# Lora-IO-Device.net
KiCad netlist of a schematic drawn in Altium Designer
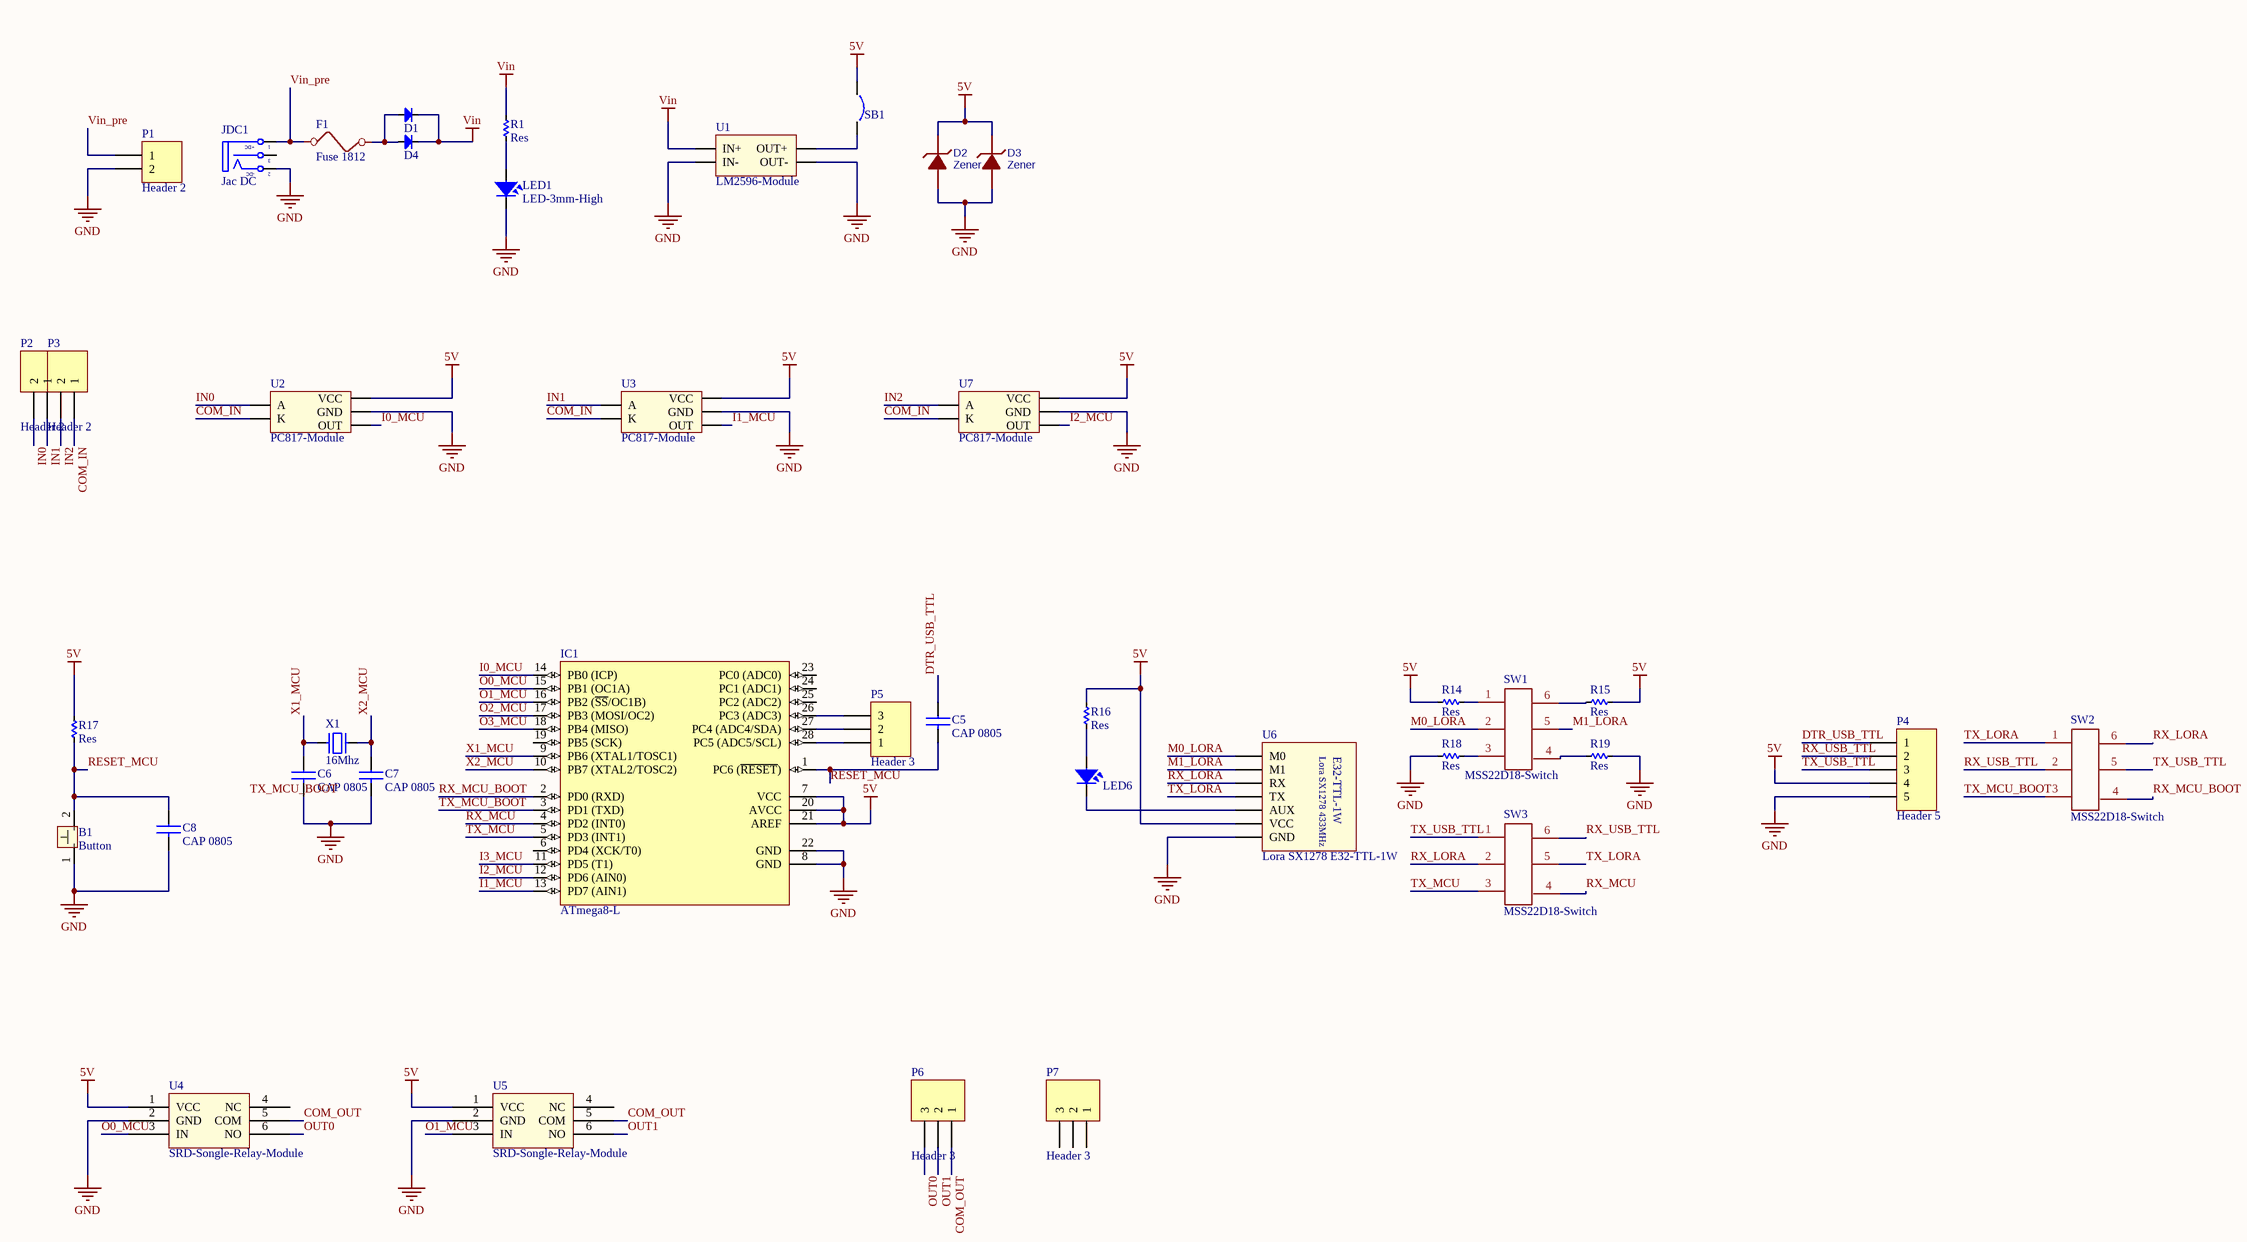
[diagram p0: Lora-IO-Device.SchDoc]

(export (version "E")
  (design (tool "Eeschema 10.0.6"))
  (components
    (comp (ref "B1")
      (value "Button")
      (footprint "Button")
      (description "Button 6x6 SMD 4 pin")
      (libsource (lib "Button SMD 6x6 4 pin") (part "Button"))
    )
    (comp (ref "C5") (value "CAP 0805") (footprint "0805") (libsource (lib "Cty1") (part "CAP 0805")))
    (comp (ref "C6") (value "CAP 0805") (footprint "0805") (libsource (lib "Cty1") (part "CAP 0805")))
    (comp (ref "C7") (value "CAP 0805") (footprint "0805") (libsource (lib "Cty1") (part "CAP 0805")))
    (comp (ref "C8") (value "CAP 0805") (footprint "0805") (libsource (lib "Cty1") (part "CAP 0805")))
    (comp (ref "D1")
      (value "Diode SMD")
      (footprint "DIO-SMD-106")
      (description "Default Diode")
      (fields (field (name "PUBLISHER") "Altium Limited"))
      (libsource (lib "Thư Viện Altium FULL HD") (part "Diode SMD"))
    )
    (comp (ref "D2")
      (value "Zener")
      (footprint "SOD80C")
      (fields
        (field (name "BOM_SUPPLIER PART") "C108433")
        (field (name "BOM_MANUFACTURER PART") "BZV55-C15")
        (field (name "CONTRIBUTOR") "LCSC")
      )
      (libsource (lib "Zener-Diode") (part "Zener"))
    )
    (comp (ref "D3")
      (value "Zener")
      (footprint "SOD80C")
      (fields
        (field (name "BOM_SUPPLIER PART") "C108433")
        (field (name "BOM_MANUFACTURER PART") "BZV55-C15")
        (field (name "CONTRIBUTOR") "LCSC")
      )
      (libsource (lib "Zener-Diode") (part "Zener"))
    )
    (comp (ref "D4")
      (value "Diode SMD")
      (footprint "DIO-SMD-106")
      (description "Default Diode")
      (fields (field (name "PUBLISHER") "Altium Limited"))
      (libsource (lib "Thư Viện Altium FULL HD") (part "Diode SMD"))
    )
    (comp (ref "F1")
      (value "Fuse 1812")
      (footprint "Fuse-1812")
      (libsource (lib "Fuse-1812") (part "Fuse-1812"))
    )
    (comp (ref "IC1")
      (value "ATmega8-L")
      (footprint "DIP28/W0.3")
      (description "8-Bit AVR Microcontroller with 8K Bytes of In-System Programmable Flash Memory")
      (libsource (lib "hphonglib") (part "ATmega8-L"))
    )
    (comp (ref "JDC1")
      (value "Jac DC")
      (footprint "DC0")
      (description "Jac DC input")
      (libsource (lib "Thư Viện Altium FULL HD") (part "DCIN"))
    )
    (comp (ref "LED1")
      (value "LED-3mm-High")
      (footprint "LED-3mm-High-Green")
      (libsource (lib "LED-3mm-High") (part "LED-3mm-High"))
    )
    (comp (ref "LED6")
      (value "LED")
      (footprint "LED-0805-Orange")
      (libsource (lib "Thư Viện Altium FULL HD") (part "LED SMD"))
    )
    (comp (ref "P1")
      (value "Header 2")
      (footprint "TBlock 2")
      (description "Header, 2-Pin")
      (fields (field (name "PUBLISHER") "Altium Limited"))
      (libsource (lib "hphonglib") (part "Header 2"))
    )
    (comp (ref "P2")
      (value "Header 2")
      (footprint "TBlock 2")
      (description "Header, 2-Pin")
      (fields (field (name "PUBLISHER") "Altium Limited"))
      (libsource (lib "hphonglib") (part "Header 2"))
    )
    (comp (ref "P3")
      (value "Header 2")
      (footprint "TBlock 2")
      (description "Header, 2-Pin")
      (fields (field (name "PUBLISHER") "Altium Limited"))
      (libsource (lib "hphonglib") (part "Header 2"))
    )
    (comp (ref "P4")
      (value "Header 5")
      (footprint "Header 5-V")
      (description "Header, 5-Pin")
      (fields (field (name "PUBLISHER") "Altium Limited"))
      (libsource (lib "hphonglib") (part "Header 5"))
    )
    (comp (ref "P5")
      (value "Header 3")
      (footprint "TBlock 3")
      (description "Header, 3-Pin")
      (fields (field (name "PUBLISHER") "Altium Limited"))
      (libsource (lib "") (part "Header 3_1"))
    )
    (comp (ref "P6")
      (value "Header 3")
      (footprint "TBlock 3")
      (description "Header, 3-Pin")
      (fields (field (name "PUBLISHER") "Altium Limited"))
      (libsource (lib "hphonglib") (part "Header 3"))
    )
    (comp (ref "P7")
      (value "Header 3")
      (footprint "TBlock 3")
      (description "Header, 3-Pin")
      (fields (field (name "PUBLISHER") "Altium Limited"))
      (libsource (lib "hphonglib") (part "Header 3"))
    )
    (comp (ref "R1")
      (value "Res")
      (footprint "RES-SMD-0805")
      (description "Resistor")
      (fields
        (field (name "MANUFACTURER") "Generic Components")
        (field (name "PUBLISHER") "Altium Hobart Technology Centre")
      )
      (libsource (lib "Thư Viện Altium FULL HD") (part "Res-SMD"))
    )
    (comp (ref "R14")
      (value "Res")
      (footprint "RES-SMD-0805")
      (description "Resistor")
      (fields
        (field (name "MANUFACTURER") "Generic Components")
        (field (name "PUBLISHER") "Altium Hobart Technology Centre")
      )
      (libsource (lib "Thư Viện Altium FULL HD") (part "Res-SMD"))
    )
    (comp (ref "R15")
      (value "Res")
      (footprint "RES-SMD-0805")
      (description "Resistor")
      (fields
        (field (name "MANUFACTURER") "Generic Components")
        (field (name "PUBLISHER") "Altium Hobart Technology Centre")
      )
      (libsource (lib "Thư Viện Altium FULL HD") (part "Res-SMD"))
    )
    (comp (ref "R16")
      (value "Res")
      (footprint "RES-SMD-0805")
      (description "Resistor")
      (fields
        (field (name "MANUFACTURER") "Generic Components")
        (field (name "PUBLISHER") "Altium Hobart Technology Centre")
      )
      (libsource (lib "Thư Viện Altium FULL HD") (part "Res-SMD"))
    )
    (comp (ref "R17")
      (value "Res")
      (footprint "RES-SMD-0805")
      (description "Resistor")
      (fields
        (field (name "MANUFACTURER") "Generic Components")
        (field (name "PUBLISHER") "Altium Hobart Technology Centre")
      )
      (libsource (lib "Thư Viện Altium FULL HD") (part "Res-SMD"))
    )
    (comp (ref "R18")
      (value "Res")
      (footprint "RES-SMD-0805")
      (description "Resistor")
      (fields
        (field (name "MANUFACTURER") "Generic Components")
        (field (name "PUBLISHER") "Altium Hobart Technology Centre")
      )
      (libsource (lib "Thư Viện Altium FULL HD") (part "Res-SMD"))
    )
    (comp (ref "R19")
      (value "Res")
      (footprint "RES-SMD-0805")
      (description "Resistor")
      (fields
        (field (name "MANUFACTURER") "Generic Components")
        (field (name "PUBLISHER") "Altium Hobart Technology Centre")
      )
      (libsource (lib "Thư Viện Altium FULL HD") (part "Res-SMD"))
    )
    (comp (ref "SB1")
      (value "Circuit-Shorter")
      (footprint "Circuit-Shorter")
      (fields (field (name "PUBLISHER") "Altium Limited"))
      (libsource (lib "Circuit-Shorter") (part "Circuit-Shorter"))
    )
    (comp (ref "SW1")
      (value "MSS22D18-Switch")
      (footprint "MSS22D18-Switch-SMD")
      (libsource (lib "MSS22D18-Switch") (part "MSS22D18-Switch"))
    )
    (comp (ref "SW2")
      (value "MSS22D18-Switch")
      (footprint "MSS22D18-Switch-SMD")
      (libsource (lib "MSS22D18-Switch") (part "MSS22D18-Switch"))
    )
    (comp (ref "SW3")
      (value "MSS22D18-Switch")
      (footprint "MSS22D18-Switch-SMD")
      (libsource (lib "MSS22D18-Switch") (part "MSS22D18-Switch"))
    )
    (comp (ref "U1")
      (value "LM2596-Module")
      (footprint "LM2596-Module-2")
      (libsource (lib "LM2596-Module") (part "LM2596-Module"))
    )
    (comp (ref "U2")
      (value "PC817-Module")
      (footprint "PC817-Module-1")
      (libsource (lib "PC817-Module") (part "PC817-Module"))
    )
    (comp (ref "U3")
      (value "PC817-Module")
      (footprint "PC817-Module-1")
      (libsource (lib "PC817-Module") (part "PC817-Module"))
    )
    (comp (ref "U4")
      (value "SRD-Songle-Relay-Module")
      (footprint "SRD-Songle-Relay-Module-1")
      (libsource (lib "SRD-Songle-Relay-Module") (part "SRD-Songle-Relay-Module"))
    )
    (comp (ref "U5")
      (value "SRD-Songle-Relay-Module")
      (footprint "SRD-Songle-Relay-Module-1")
      (libsource (lib "SRD-Songle-Relay-Module") (part "SRD-Songle-Relay-Module"))
    )
    (comp (ref "U6")
      (value "Lora SX1278 E32-TTL-1W")
      (footprint "Lora SX1278 E32-TTL-1W")
      (libsource (lib "Lora SX1278 E32-TTL-1W") (part "Lora SX1278 E32-TTL-1W"))
    )
    (comp (ref "U7")
      (value "PC817-Module")
      (footprint "PC817-Module-1")
      (libsource (lib "PC817-Module") (part "PC817-Module"))
    )
    (comp (ref "X1")
      (value "16Mhz")
      (footprint "XTAL-RU49/4")
      (description "Crystal, 32.768 KHz, -40 to 85 degC, 3.2 x 1.5 x 0.9 mm SMD")
      (libsource (lib "Thư Viện Altium FULL HD") (part "XT2"))
    )
  )
  (nets
    (net (code "1") (name "/COM_IN") (class "Default")
      (node (ref "P3") (pin "1") (pinfunction "1_1") (pintype "passive"))
      (node (ref "U2") (pin "2") (pinfunction "K_2") (pintype "passive"))
      (node (ref "U3") (pin "2") (pinfunction "K_2") (pintype "passive"))
      (node (ref "U7") (pin "2") (pinfunction "K_2") (pintype "passive"))
    )
    (net (code "2") (name "/COM_OUT") (class "Default")
      (node (ref "P6") (pin "1") (pinfunction "1_1") (pintype "passive"))
      (node (ref "U4") (pin "5") (pinfunction "COM_5") (pintype "passive"))
      (node (ref "U5") (pin "5") (pinfunction "COM_5") (pintype "passive"))
    )
    (net (code "3") (name "/DTR_USB_TTL") (class "Default")
      (node (ref "C5") (pin "1") (pinfunction "1_1") (pintype "passive"))
      (node (ref "P4") (pin "1") (pinfunction "1_1") (pintype "passive"))
    )
    (net (code "4") (name "/I0_MCU") (class "Default")
      (node (ref "IC1") (pin "14") (pinfunction "PB0_(ICP)_14") (pintype "bidirectional"))
      (node (ref "U2") (pin "5") (pinfunction "OUT_5") (pintype "passive"))
    )
    (net (code "5") (name "/I1_MCU") (class "Default")
      (node (ref "IC1") (pin "13") (pinfunction "PD7_(AIN1)_13") (pintype "bidirectional"))
      (node (ref "U3") (pin "5") (pinfunction "OUT_5") (pintype "passive"))
    )
    (net (code "6") (name "/I2_MCU") (class "Default")
      (node (ref "IC1") (pin "12") (pinfunction "PD6_(AIN0)_12") (pintype "bidirectional"))
      (node (ref "U7") (pin "5") (pinfunction "OUT_5") (pintype "passive"))
    )
    (net (code "7") (name "/I3_MCU") (class "Default")
      (node (ref "IC1") (pin "11") (pinfunction "PD5_(T1)_11") (pintype "bidirectional"))
    )
    (net (code "8") (name "/IN0") (class "Default")
      (node (ref "P2") (pin "2") (pinfunction "2_2") (pintype "passive"))
      (node (ref "U2") (pin "1") (pinfunction "A_1") (pintype "passive"))
    )
    (net (code "9") (name "/IN1") (class "Default")
      (node (ref "P2") (pin "1") (pinfunction "1_1") (pintype "passive"))
      (node (ref "U3") (pin "1") (pinfunction "A_1") (pintype "passive"))
    )
    (net (code "10") (name "/IN2") (class "Default")
      (node (ref "P3") (pin "2") (pinfunction "2_2") (pintype "passive"))
      (node (ref "U7") (pin "1") (pinfunction "A_1") (pintype "passive"))
    )
    (net (code "11") (name "/M0_LORA") (class "Default")
      (node (ref "SW1") (pin "2") (pinfunction "2_2") (pintype "passive"))
      (node (ref "U6") (pin "1") (pinfunction "M0_1") (pintype "passive"))
    )
    (net (code "12") (name "/M1_LORA") (class "Default")
      (node (ref "SW1") (pin "5") (pinfunction "5_5") (pintype "passive"))
      (node (ref "U6") (pin "2") (pinfunction "M1_2") (pintype "passive"))
    )
    (net (code "13") (name "/O0_MCU") (class "Default")
      (node (ref "IC1") (pin "15") (pinfunction "PB1_(OC1A)_15") (pintype "bidirectional"))
      (node (ref "U4") (pin "3") (pinfunction "IN_3") (pintype "passive"))
    )
    (net (code "14") (name "/O1_MCU") (class "Default")
      (node (ref "IC1") (pin "16") (pinfunction "PB2_(~{SS}/OC1B)_16") (pintype "bidirectional"))
      (node (ref "U5") (pin "3") (pinfunction "IN_3") (pintype "passive"))
    )
    (net (code "15") (name "/O2_MCU") (class "Default")
      (node (ref "IC1") (pin "17") (pinfunction "PB3_(MOSI/OC2)_17") (pintype "bidirectional"))
    )
    (net (code "16") (name "/O3_MCU") (class "Default")
      (node (ref "IC1") (pin "18") (pinfunction "PB4_(MISO)_18") (pintype "bidirectional"))
    )
    (net (code "17") (name "/OUT0") (class "Default")
      (node (ref "P6") (pin "3") (pinfunction "3_3") (pintype "passive"))
      (node (ref "U4") (pin "6") (pinfunction "NO_6") (pintype "passive"))
    )
    (net (code "18") (name "/OUT1") (class "Default")
      (node (ref "P6") (pin "2") (pinfunction "2_2") (pintype "passive"))
      (node (ref "U5") (pin "6") (pinfunction "NO_6") (pintype "passive"))
    )
    (net (code "19") (name "/RESET_MCU") (class "Default")
      (node (ref "B1") (pin "2") (pinfunction "2_2") (pintype "passive"))
      (node (ref "C5") (pin "2") (pinfunction "2_2") (pintype "passive"))
      (node (ref "C8") (pin "1") (pinfunction "1_1") (pintype "passive"))
      (node (ref "IC1") (pin "1") (pinfunction "PC6_(~{RESET})_1") (pintype "bidirectional"))
      (node (ref "R17") (pin "2") (pinfunction "2_2") (pintype "passive"))
    )
    (net (code "20") (name "/RX_LORA") (class "Default")
      (node (ref "SW2") (pin "6") (pinfunction "6_6") (pintype "passive"))
      (node (ref "SW3") (pin "2") (pinfunction "2_2") (pintype "passive"))
      (node (ref "U6") (pin "3") (pinfunction "RX_3") (pintype "passive"))
    )
    (net (code "21") (name "/RX_MCU") (class "Default")
      (node (ref "IC1") (pin "4") (pinfunction "PD2_(INT0)_4") (pintype "bidirectional"))
      (node (ref "SW3") (pin "4") (pinfunction "4_4") (pintype "passive"))
    )
    (net (code "22") (name "/RX_MCU_BOOT") (class "Default")
      (node (ref "IC1") (pin "2") (pinfunction "PD0_(RXD)_2") (pintype "bidirectional"))
      (node (ref "SW2") (pin "4") (pinfunction "4_4") (pintype "passive"))
    )
    (net (code "23") (name "/RX_USB_TTL") (class "Default")
      (node (ref "P4") (pin "2") (pinfunction "2_2") (pintype "passive"))
      (node (ref "SW2") (pin "2") (pinfunction "2_2") (pintype "passive"))
      (node (ref "SW3") (pin "6") (pinfunction "6_6") (pintype "passive"))
    )
    (net (code "24") (name "/TX_LORA") (class "Default")
      (node (ref "SW2") (pin "1") (pinfunction "1_1") (pintype "passive"))
      (node (ref "SW3") (pin "5") (pinfunction "5_5") (pintype "passive"))
      (node (ref "U6") (pin "4") (pinfunction "TX_4") (pintype "passive"))
    )
    (net (code "25") (name "/TX_MCU") (class "Default")
      (node (ref "IC1") (pin "5") (pinfunction "PD3_(INT1)_5") (pintype "bidirectional"))
      (node (ref "SW3") (pin "3") (pinfunction "3_3") (pintype "passive"))
    )
    (net (code "26") (name "/TX_MCU_BOOT") (class "Default")
      (node (ref "IC1") (pin "3") (pinfunction "PD1_(TXD)_3") (pintype "bidirectional"))
      (node (ref "SW2") (pin "3") (pinfunction "3_3") (pintype "passive"))
    )
    (net (code "27") (name "/TX_USB_TTL") (class "Default")
      (node (ref "P4") (pin "3") (pinfunction "3_3") (pintype "passive"))
      (node (ref "SW2") (pin "5") (pinfunction "5_5") (pintype "passive"))
      (node (ref "SW3") (pin "1") (pinfunction "1_1") (pintype "passive"))
    )
    (net (code "28") (name "/Vin_pre") (class "Default")
      (node (ref "F1") (pin "1") (pinfunction "1_1") (pintype "passive"))
      (node (ref "JDC1") (pin "1") (pinfunction "T_1") (pintype "passive"))
      (node (ref "P1") (pin "1") (pinfunction "1_1") (pintype "passive"))
    )
    (net (code "29") (name "/X1_MCU") (class "Default")
      (node (ref "C6") (pin "1") (pinfunction "1_1") (pintype "passive"))
      (node (ref "IC1") (pin "9") (pinfunction "PB6_(XTAL1/TOSC1)_9") (pintype "bidirectional"))
      (node (ref "X1") (pin "1") (pinfunction "1_1") (pintype "passive"))
    )
    (net (code "30") (name "/X2_MCU") (class "Default")
      (node (ref "C7") (pin "1") (pinfunction "1_1") (pintype "passive"))
      (node (ref "IC1") (pin "10") (pinfunction "PB7_(XTAL2/TOSC2)_10") (pintype "bidirectional"))
      (node (ref "X1") (pin "2") (pinfunction "2_2") (pintype "passive"))
    )
    (net (code "31") (name "5V") (class "Default")
      (node (ref "D2") (pin "2") (pinfunction "K_2") (pintype "passive"))
      (node (ref "D3") (pin "2") (pinfunction "K_2") (pintype "passive"))
      (node (ref "IC1") (pin "20") (pinfunction "AVCC_20") (pintype "power_in"))
      (node (ref "IC1") (pin "21") (pinfunction "AREF_21") (pintype "passive"))
      (node (ref "IC1") (pin "7") (pinfunction "VCC_7") (pintype "power_in"))
      (node (ref "P4") (pin "4") (pinfunction "4_4") (pintype "passive"))
      (node (ref "R14") (pin "2") (pinfunction "2_2") (pintype "passive"))
      (node (ref "R15") (pin "1") (pinfunction "1_1") (pintype "passive"))
      (node (ref "R16") (pin "1") (pinfunction "1_1") (pintype "passive"))
      (node (ref "R17") (pin "1") (pinfunction "1_1") (pintype "passive"))
      (node (ref "SB1") (pin "1") (pinfunction "1_1") (pintype "passive"))
      (node (ref "U2") (pin "3") (pinfunction "VCC_3") (pintype "passive"))
      (node (ref "U3") (pin "3") (pinfunction "VCC_3") (pintype "passive"))
      (node (ref "U4") (pin "1") (pinfunction "VCC_1") (pintype "passive"))
      (node (ref "U5") (pin "1") (pinfunction "VCC_1") (pintype "passive"))
      (node (ref "U6") (pin "6") (pinfunction "VCC_6") (pintype "passive"))
      (node (ref "U7") (pin "3") (pinfunction "VCC_3") (pintype "passive"))
    )
    (net (code "32") (name "GND") (class "Default")
      (node (ref "B1") (pin "1") (pinfunction "1_1") (pintype "passive"))
      (node (ref "C6") (pin "2") (pinfunction "2_2") (pintype "passive"))
      (node (ref "C7") (pin "2") (pinfunction "2_2") (pintype "passive"))
      (node (ref "C8") (pin "2") (pinfunction "2_2") (pintype "passive"))
      (node (ref "D2") (pin "1") (pinfunction "A_1") (pintype "passive"))
      (node (ref "D3") (pin "1") (pinfunction "A_1") (pintype "passive"))
      (node (ref "IC1") (pin "22") (pinfunction "GND_22") (pintype "power_in"))
      (node (ref "IC1") (pin "8") (pinfunction "GND_8") (pintype "power_in"))
      (node (ref "JDC1") (pin "2") (pinfunction "TN_2") (pintype "passive"))
      (node (ref "LED1") (pin "2") (pinfunction "K_2") (pintype "passive"))
      (node (ref "P1") (pin "2") (pinfunction "2_2") (pintype "passive"))
      (node (ref "P4") (pin "5") (pinfunction "5_5") (pintype "passive"))
      (node (ref "R18") (pin "2") (pinfunction "2_2") (pintype "passive"))
      (node (ref "R19") (pin "1") (pinfunction "1_1") (pintype "passive"))
      (node (ref "U1") (pin "IN-") (pinfunction "IN-_IN-") (pintype "passive"))
      (node (ref "U1") (pin "OUT-") (pinfunction "OUT-_OUT-") (pintype "passive"))
      (node (ref "U2") (pin "4") (pinfunction "GND_4") (pintype "passive"))
      (node (ref "U3") (pin "4") (pinfunction "GND_4") (pintype "passive"))
      (node (ref "U4") (pin "2") (pinfunction "GND_2") (pintype "passive"))
      (node (ref "U5") (pin "2") (pinfunction "GND_2") (pintype "passive"))
      (node (ref "U6") (pin "7") (pinfunction "GND_7") (pintype "passive"))
      (node (ref "U7") (pin "4") (pinfunction "GND_4") (pintype "passive"))
    )
    (net (code "33") (name "Net-(D1-A)") (class "Default")
      (node (ref "D1") (pin "1") (pinfunction "A_1") (pintype "passive"))
      (node (ref "D4") (pin "1") (pinfunction "A_1") (pintype "passive"))
      (node (ref "F1") (pin "2") (pinfunction "2_2") (pintype "passive"))
    )
    (net (code "34") (name "Net-(IC1-PC3_(ADC3))") (class "Default")
      (node (ref "IC1") (pin "26") (pinfunction "PC3_(ADC3)_26") (pintype "bidirectional"))
      (node (ref "P5") (pin "3") (pinfunction "3_3") (pintype "passive"))
    )
    (net (code "35") (name "Net-(IC1-PC4_(ADC4{slash}SDA))") (class "Default")
      (node (ref "IC1") (pin "27") (pinfunction "PC4_(ADC4/SDA)_27") (pintype "bidirectional"))
      (node (ref "P5") (pin "2") (pinfunction "2_2") (pintype "passive"))
    )
    (net (code "36") (name "Net-(IC1-PC5_(ADC5{slash}SCL))") (class "Default")
      (node (ref "IC1") (pin "28") (pinfunction "PC5_(ADC5/SCL)_28") (pintype "bidirectional"))
      (node (ref "P5") (pin "1") (pinfunction "1_1") (pintype "passive"))
    )
    (net (code "37") (name "Net-(LED1-A)") (class "Default")
      (node (ref "LED1") (pin "1") (pinfunction "A_1") (pintype "passive"))
      (node (ref "R1") (pin "2") (pinfunction "2_2") (pintype "passive"))
    )
    (net (code "38") (name "Net-(LED6-Pad1)") (class "Default")
      (node (ref "LED6") (pin "1") (pinfunction "1_1") (pintype "passive"))
      (node (ref "R16") (pin "2") (pinfunction "2_2") (pintype "passive"))
    )
    (net (code "39") (name "Net-(R14-Pad1)") (class "Default")
      (node (ref "R14") (pin "1") (pinfunction "1_1") (pintype "passive"))
      (node (ref "SW1") (pin "1") (pinfunction "1_1") (pintype "passive"))
    )
    (net (code "40") (name "Net-(R15-Pad2)") (class "Default")
      (node (ref "R15") (pin "2") (pinfunction "2_2") (pintype "passive"))
      (node (ref "SW1") (pin "6") (pinfunction "6_6") (pintype "passive"))
    )
    (net (code "41") (name "Net-(R18-Pad1)") (class "Default")
      (node (ref "R18") (pin "1") (pinfunction "1_1") (pintype "passive"))
      (node (ref "SW1") (pin "3") (pinfunction "3_3") (pintype "passive"))
    )
    (net (code "42") (name "Net-(R19-Pad2)") (class "Default")
      (node (ref "R19") (pin "2") (pinfunction "2_2") (pintype "passive"))
      (node (ref "SW1") (pin "4") (pinfunction "4_4") (pintype "passive"))
    )
    (net (code "43") (name "Net-(SB1-Pad2)") (class "Default")
      (node (ref "SB1") (pin "2") (pinfunction "2_2") (pintype "passive"))
      (node (ref "U1") (pin "OUT+") (pinfunction "OUT+_OUT+") (pintype "passive"))
    )
    (net (code "44") (name "Net-(U6-AUX)") (class "Default")
      (node (ref "LED6") (pin "2") (pinfunction "2_2") (pintype "passive"))
      (node (ref "U6") (pin "5") (pinfunction "AUX_5") (pintype "passive"))
    )
    (net (code "45") (name "Vin") (class "Default")
      (node (ref "D1") (pin "2") (pinfunction "K_2") (pintype "passive"))
      (node (ref "D4") (pin "2") (pinfunction "K_2") (pintype "passive"))
      (node (ref "R1") (pin "1") (pinfunction "1_1") (pintype "passive"))
      (node (ref "U1") (pin "IN+") (pinfunction "IN+_IN+") (pintype "passive"))
    )
    (net (code "46") (name "unconnected-(IC1-PB5_(SCK)-Pad19)") (class "Default")
      (node (ref "IC1") (pin "19") (pinfunction "PB5_(SCK)_19") (pintype "bidirectional"))
    )
    (net (code "47") (name "unconnected-(IC1-PC0_(ADC0)-Pad23)") (class "Default")
      (node (ref "IC1") (pin "23") (pinfunction "PC0_(ADC0)_23") (pintype "bidirectional"))
    )
    (net (code "48") (name "unconnected-(IC1-PC1_(ADC1)-Pad24)") (class "Default")
      (node (ref "IC1") (pin "24") (pinfunction "PC1_(ADC1)_24") (pintype "bidirectional"))
    )
    (net (code "49") (name "unconnected-(IC1-PC2_(ADC2)-Pad25)") (class "Default")
      (node (ref "IC1") (pin "25") (pinfunction "PC2_(ADC2)_25") (pintype "bidirectional"))
    )
    (net (code "50") (name "unconnected-(IC1-PD4_(XCK{slash}T0)-Pad6)") (class "Default")
      (node (ref "IC1") (pin "6") (pinfunction "PD4_(XCK/T0)_6") (pintype "bidirectional"))
    )
    (net (code "51") (name "unconnected-(JDC1-S-Pad3)") (class "Default")
      (node (ref "JDC1") (pin "3") (pinfunction "S_3") (pintype "power_in"))
    )
    (net (code "52") (name "unconnected-(P7-Pad1)") (class "Default")
      (node (ref "P7") (pin "1") (pinfunction "1_1") (pintype "passive"))
    )
    (net (code "53") (name "unconnected-(P7-Pad2)") (class "Default")
      (node (ref "P7") (pin "2") (pinfunction "2_2") (pintype "passive"))
    )
    (net (code "54") (name "unconnected-(P7-Pad3)") (class "Default")
      (node (ref "P7") (pin "3") (pinfunction "3_3") (pintype "passive"))
    )
    (net (code "55") (name "unconnected-(U4-NC-Pad4)") (class "Default")
      (node (ref "U4") (pin "4") (pinfunction "NC_4") (pintype "passive"))
    )
    (net (code "56") (name "unconnected-(U5-NC-Pad4)") (class "Default")
      (node (ref "U5") (pin "4") (pinfunction "NC_4") (pintype "passive"))
    )
  )
)
